# Main.net
KiCad netlist of a schematic drawn in EAGLE
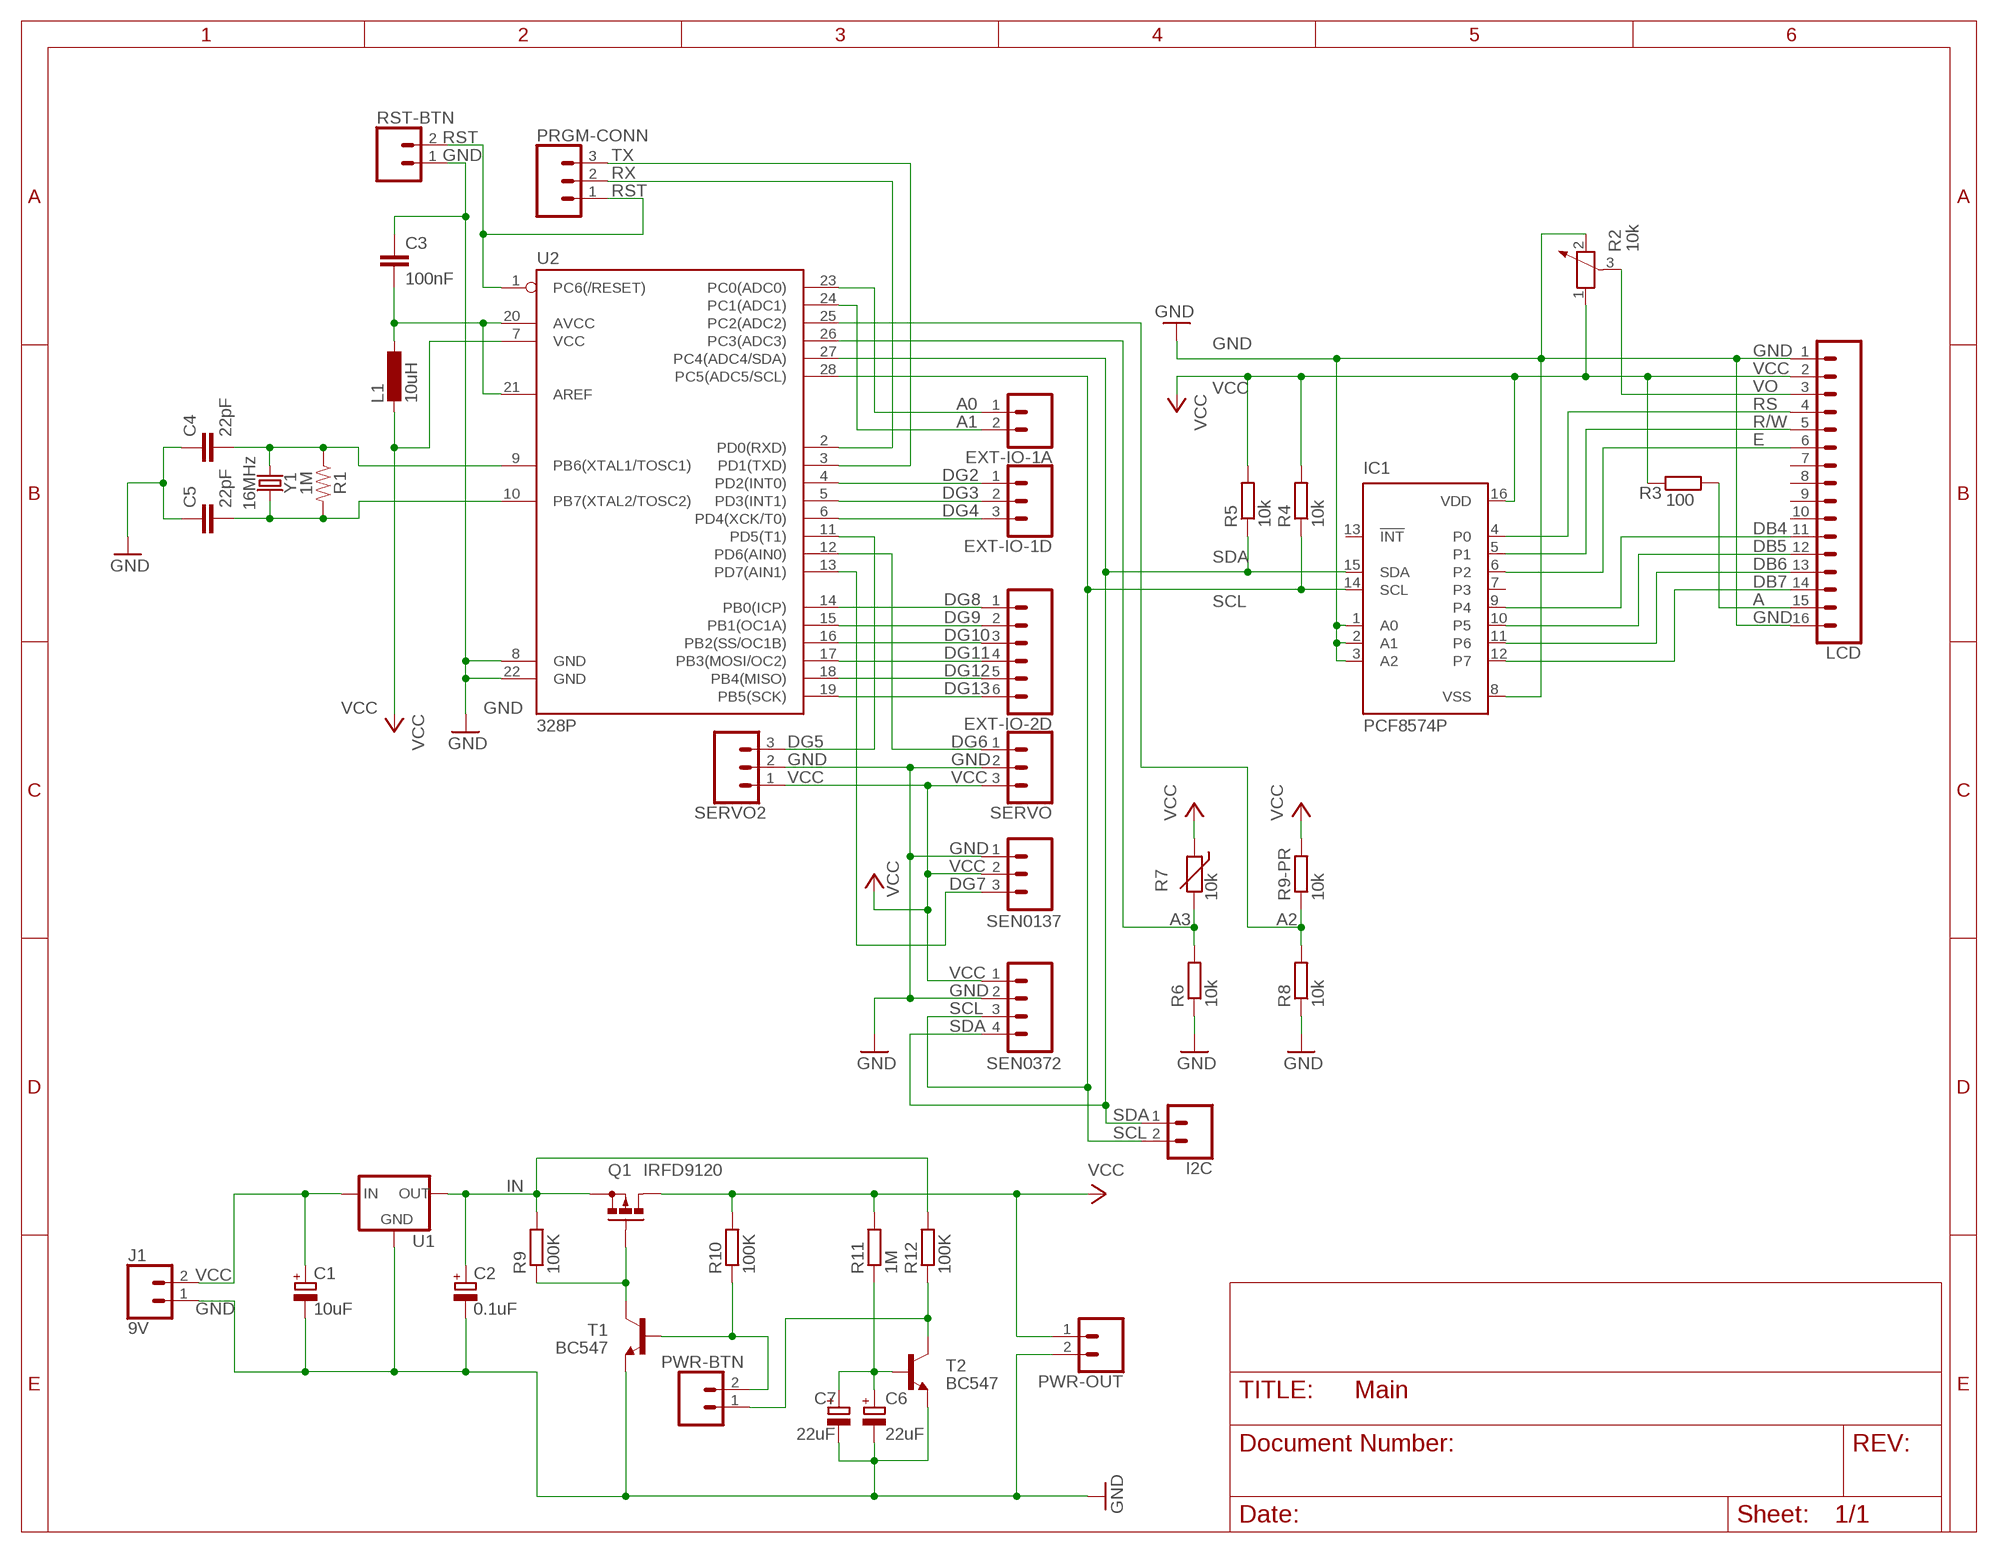
[diagram p0: schematic, sheet 1]

(export (version "E")
  (design (tool "Eeschema 10.0.6"))
  (components
    (comp (ref "C1")
      (value "10uF")
      (footprint "eagle-import:E2,5-5")
      (libsource (lib "eagle-import") (part "CPOL-EUE2.5-5"))
    )
    (comp (ref "C2")
      (value "0.1uF")
      (footprint "eagle-import:E2-4")
      (libsource (lib "eagle-import") (part "CPOL-EUE2-4"))
    )
    (comp (ref "C3")
      (value "100nF")
      (footprint "eagle-import:C050-025X075")
      (libsource (lib "eagle-import") (part "C-EU050-025X075"))
    )
    (comp (ref "C4")
      (value "22pF")
      (footprint "eagle-import:CAP-PTH-2.54")
      (libsource (lib "eagle-import") (part "22PF-PTH-2.54MM-200V-5%"))
    )
    (comp (ref "C5")
      (value "22pF")
      (footprint "eagle-import:CAP-PTH-2.54")
      (libsource (lib "eagle-import") (part "22PF-PTH-2.54MM-200V-5%"))
    )
    (comp (ref "C6")
      (value "22uF")
      (footprint "eagle-import:E2-5")
      (libsource (lib "eagle-import") (part "CPOL-EUE2-5"))
    )
    (comp (ref "C7")
      (value "22uF")
      (footprint "eagle-import:E2-5")
      (libsource (lib "eagle-import") (part "CPOL-EUE2-5"))
    )
    (comp (ref "EXT-IO-1A")
      (value "CONN_02LOCK_LONGPADS")
      (footprint "eagle-import:1X02_LOCK_LONGPADS")
      (libsource (lib "eagle-import") (part "CONN_02LOCK_LONGPADS"))
    )
    (comp (ref "EXT-IO-1D")
      (value "CONN_03LONGPADS")
      (footprint "eagle-import:1X03_LONGPADS")
      (libsource (lib "eagle-import") (part "CONN_03LONGPADS"))
    )
    (comp (ref "EXT-IO-2D")
      (value "CONN_06LONGPADS")
      (footprint "eagle-import:1X06_LONGPADS")
      (libsource (lib "eagle-import") (part "CONN_06LONGPADS"))
    )
    (comp (ref "I2C")
      (value "CONN_02LOCK_LONGPADS")
      (footprint "eagle-import:1X02_LOCK_LONGPADS")
      (libsource (lib "eagle-import") (part "CONN_02LOCK_LONGPADS"))
    )
    (comp (ref "IC1")
      (value "PCF8574P")
      (footprint "eagle-import:DIL16")
      (fields (field (name "MPN") "PCF8574PN"))
      (libsource (lib "eagle-import") (part "PCF8574P"))
    )
    (comp (ref "J1")
      (value "9V")
      (footprint "eagle-import:1X02_LOCK_LONGPADS")
      (libsource (lib "eagle-import") (part "CONN_02LOCK_LONGPADS"))
    )
    (comp (ref "L1")
      (value "10uH")
      (footprint "eagle-import:0204_5")
      (libsource (lib "eagle-import") (part "L-EU0204/5"))
    )
    (comp (ref "LCD")
      (value "CONN_16LONGPADS")
      (footprint "eagle-import:1X16_LONGPADS")
      (libsource (lib "eagle-import") (part "CONN_16LONGPADS"))
    )
    (comp (ref "PRGM-CONN")
      (value "CONN_03LONGPADS")
      (footprint "eagle-import:1X03_LONGPADS")
      (libsource (lib "eagle-import") (part "CONN_03LONGPADS"))
    )
    (comp (ref "PWR-BTN")
      (value "CONN_02LOCK_LONGPADS")
      (footprint "eagle-import:1X02_LOCK_LONGPADS")
      (libsource (lib "eagle-import") (part "CONN_02LOCK_LONGPADS"))
    )
    (comp (ref "PWR-OUT")
      (value "CONN_02LOCK_LONGPADS")
      (footprint "eagle-import:1X02_LOCK_LONGPADS")
      (libsource (lib "eagle-import") (part "CONN_02LOCK_LONGPADS"))
    )
    (comp (ref "Q1")
      (value "IRFD9120")
      (footprint "eagle-import:C370-01")
      (libsource (lib "eagle-import") (part "IRFD9120"))
    )
    (comp (ref "R1")
      (value "1M")
      (footprint "eagle-import:AXIAL-0.3")
      (libsource (lib "eagle-import") (part "RESISTORAXIAL-0.3"))
    )
    (comp (ref "R2")
      (value "10k")
      (footprint "eagle-import:PT-10")
      (libsource (lib "eagle-import") (part "POTENTIOMETER_PT-10"))
    )
    (comp (ref "R3")
      (value "100")
      (footprint "eagle-import:0207_10")
      (libsource (lib "eagle-import") (part "R-EU_0207/10"))
    )
    (comp (ref "R4")
      (value "10k")
      (footprint "eagle-import:0207_10")
      (libsource (lib "eagle-import") (part "R-EU_0207/10"))
    )
    (comp (ref "R5")
      (value "10k")
      (footprint "eagle-import:0207_10")
      (libsource (lib "eagle-import") (part "R-EU_0207/10"))
    )
    (comp (ref "R6")
      (value "10k")
      (footprint "eagle-import:0207_10")
      (libsource (lib "eagle-import") (part "R-EU_0207/10"))
    )
    (comp (ref "R7")
      (value "10k")
      (footprint "eagle-import:RS-2,5")
      (libsource (lib "eagle-import") (part "THERMISTOR-2,5"))
    )
    (comp (ref "R8")
      (value "10k")
      (footprint "eagle-import:0207_10")
      (libsource (lib "eagle-import") (part "R-EU_0207/10"))
    )
    (comp (ref "R9")
      (value "100K")
      (footprint "eagle-import:0207_10")
      (libsource (lib "eagle-import") (part "R-EU_0207/10"))
    )
    (comp (ref "R9-PR")
      (value "10k")
      (footprint "eagle-import:0204V")
      (libsource (lib "eagle-import") (part "R-EU_0204/2V"))
    )
    (comp (ref "R10")
      (value "100K")
      (footprint "eagle-import:0207_10")
      (libsource (lib "eagle-import") (part "R-EU_0207/10"))
    )
    (comp (ref "R11")
      (value "1M")
      (footprint "eagle-import:0207_10")
      (libsource (lib "eagle-import") (part "R-EU_0207/10"))
    )
    (comp (ref "R12")
      (value "100K")
      (footprint "eagle-import:0207_10")
      (libsource (lib "eagle-import") (part "R-EU_0207/10"))
    )
    (comp (ref "RST-BTN")
      (value "CONN_02LOCK_LONGPADS")
      (footprint "eagle-import:1X02_LOCK_LONGPADS")
      (libsource (lib "eagle-import") (part "CONN_02LOCK_LONGPADS"))
    )
    (comp (ref "SEN0137")
      (value "CONN_03LONGPADS")
      (footprint "eagle-import:1X03_LONGPADS")
      (libsource (lib "eagle-import") (part "CONN_03LONGPADS"))
    )
    (comp (ref "SEN0372")
      (value "CONN_04LONGPADS")
      (footprint "eagle-import:1X04_LONGPADS")
      (libsource (lib "eagle-import") (part "CONN_04LONGPADS"))
    )
    (comp (ref "SERVO")
      (value "CONN_03LONGPADS")
      (footprint "eagle-import:1X03_LONGPADS")
      (libsource (lib "eagle-import") (part "CONN_03LONGPADS"))
    )
    (comp (ref "SERVO2")
      (value "CONN_03LONGPADS")
      (footprint "eagle-import:1X03_LONGPADS")
      (libsource (lib "eagle-import") (part "CONN_03LONGPADS"))
    )
    (comp (ref "T1")
      (value "BC547")
      (footprint "eagle-import:TO92")
      (libsource (lib "eagle-import") (part "BC547"))
    )
    (comp (ref "T2")
      (value "BC547")
      (footprint "eagle-import:TO92")
      (libsource (lib "eagle-import") (part "BC547"))
    )
    (comp (ref "U1")
      (value "V_REG_78XX-TO-220")
      (footprint "eagle-import:TO-220-ALT")
      (libsource (lib "eagle-import") (part "V_REG_78XX-TO-220"))
    )
    (comp (ref "U2")
      (value "328P")
      (footprint "eagle-import:DIP28")
      (libsource (lib "eagle-import") (part "ATMEGA328P_PDIP"))
    )
    (comp (ref "Y1")
      (value "16MHz")
      (footprint "eagle-import:HC49US")
      (libsource (lib "eagle-import") (part "CRYSTAL-16MHZPTH-HC49US"))
    )
  )
  (nets
    (net (code "1") (name "/A") (class "Default")
      (node (ref "LCD") (pin "15") (pinfunction "15_15") (pintype "passive"))
      (node (ref "R3") (pin "2") (pinfunction "2_2") (pintype "passive"))
    )
    (net (code "2") (name "/A0") (class "Default")
      (node (ref "EXT-IO-1A") (pin "1") (pinfunction "1_1") (pintype "passive"))
      (node (ref "U2") (pin "23") (pinfunction "PC0(ADC0)_23") (pintype "bidirectional"))
    )
    (net (code "3") (name "/A1") (class "Default")
      (node (ref "EXT-IO-1A") (pin "2") (pinfunction "2_2") (pintype "passive"))
      (node (ref "U2") (pin "24") (pinfunction "PC1(ADC1)_24") (pintype "bidirectional"))
    )
    (net (code "4") (name "/A2") (class "Default")
      (node (ref "R8") (pin "2") (pinfunction "2_2") (pintype "passive"))
      (node (ref "R9-PR") (pin "1") (pinfunction "1_1") (pintype "passive"))
      (node (ref "U2") (pin "25") (pinfunction "PC2(ADC2)_25") (pintype "bidirectional"))
    )
    (net (code "5") (name "/A3") (class "Default")
      (node (ref "R6") (pin "2") (pinfunction "2_2") (pintype "passive"))
      (node (ref "R7") (pin "2") (pinfunction "2_2") (pintype "passive"))
      (node (ref "U2") (pin "26") (pinfunction "PC3(ADC3)_26") (pintype "bidirectional"))
    )
    (net (code "6") (name "/DB4") (class "Default")
      (node (ref "IC1") (pin "9") (pinfunction "P4_9") (pintype "bidirectional"))
      (node (ref "LCD") (pin "11") (pinfunction "11_11") (pintype "passive"))
    )
    (net (code "7") (name "/DB5") (class "Default")
      (node (ref "IC1") (pin "10") (pinfunction "P5_10") (pintype "bidirectional"))
      (node (ref "LCD") (pin "12") (pinfunction "12_12") (pintype "passive"))
    )
    (net (code "8") (name "/DB6") (class "Default")
      (node (ref "IC1") (pin "11") (pinfunction "P6_11") (pintype "bidirectional"))
      (node (ref "LCD") (pin "13") (pinfunction "13_13") (pintype "passive"))
    )
    (net (code "9") (name "/DB7") (class "Default")
      (node (ref "IC1") (pin "12") (pinfunction "P7_12") (pintype "bidirectional"))
      (node (ref "LCD") (pin "14") (pinfunction "14_14") (pintype "passive"))
    )
    (net (code "10") (name "/DG2") (class "Default")
      (node (ref "EXT-IO-1D") (pin "1") (pinfunction "1_1") (pintype "passive"))
      (node (ref "U2") (pin "4") (pinfunction "PD2(INT0)_4") (pintype "bidirectional"))
    )
    (net (code "11") (name "/DG3") (class "Default")
      (node (ref "EXT-IO-1D") (pin "2") (pinfunction "2_2") (pintype "passive"))
      (node (ref "U2") (pin "5") (pinfunction "PD3(INT1)_5") (pintype "bidirectional"))
    )
    (net (code "12") (name "/DG4") (class "Default")
      (node (ref "EXT-IO-1D") (pin "3") (pinfunction "3_3") (pintype "passive"))
      (node (ref "U2") (pin "6") (pinfunction "PD4(XCK/T0)_6") (pintype "bidirectional"))
    )
    (net (code "13") (name "/DG5") (class "Default")
      (node (ref "SERVO2") (pin "3") (pinfunction "3_3") (pintype "passive"))
      (node (ref "U2") (pin "11") (pinfunction "PD5(T1)_11") (pintype "bidirectional"))
    )
    (net (code "14") (name "/DG6") (class "Default")
      (node (ref "SERVO") (pin "1") (pinfunction "1_1") (pintype "passive"))
      (node (ref "U2") (pin "12") (pinfunction "PD6(AIN0)_12") (pintype "bidirectional"))
    )
    (net (code "15") (name "/DG7") (class "Default")
      (node (ref "SEN0137") (pin "3") (pinfunction "3_3") (pintype "passive"))
      (node (ref "U2") (pin "13") (pinfunction "PD7(AIN1)_13") (pintype "bidirectional"))
    )
    (net (code "16") (name "/DG8") (class "Default")
      (node (ref "EXT-IO-2D") (pin "1") (pinfunction "1_1") (pintype "passive"))
      (node (ref "U2") (pin "14") (pinfunction "PB0(ICP)_14") (pintype "bidirectional"))
    )
    (net (code "17") (name "/DG9") (class "Default")
      (node (ref "EXT-IO-2D") (pin "2") (pinfunction "2_2") (pintype "passive"))
      (node (ref "U2") (pin "15") (pinfunction "PB1(OC1A)_15") (pintype "bidirectional"))
    )
    (net (code "18") (name "/DG10") (class "Default")
      (node (ref "EXT-IO-2D") (pin "3") (pinfunction "3_3") (pintype "passive"))
      (node (ref "U2") (pin "16") (pinfunction "PB2(SS/OC1B)_16") (pintype "bidirectional"))
    )
    (net (code "19") (name "/DG11") (class "Default")
      (node (ref "EXT-IO-2D") (pin "4") (pinfunction "4_4") (pintype "passive"))
      (node (ref "U2") (pin "17") (pinfunction "PB3(MOSI/OC2)_17") (pintype "bidirectional"))
    )
    (net (code "20") (name "/DG12") (class "Default")
      (node (ref "EXT-IO-2D") (pin "5") (pinfunction "5_5") (pintype "passive"))
      (node (ref "U2") (pin "18") (pinfunction "PB4(MISO)_18") (pintype "bidirectional"))
    )
    (net (code "21") (name "/DG13") (class "Default")
      (node (ref "EXT-IO-2D") (pin "6") (pinfunction "6_6") (pintype "passive"))
      (node (ref "U2") (pin "19") (pinfunction "PB5(SCK)_19") (pintype "bidirectional"))
    )
    (net (code "22") (name "/E") (class "Default")
      (node (ref "IC1") (pin "6") (pinfunction "P2_6") (pintype "bidirectional"))
      (node (ref "LCD") (pin "6") (pinfunction "6_6") (pintype "passive"))
    )
    (net (code "23") (name "/IN") (class "Default")
      (node (ref "C2") (pin "+") (pinfunction "+_+") (pintype "passive"))
      (node (ref "Q1") (pin "S") (pinfunction "S_S") (pintype "passive"))
      (node (ref "R12") (pin "2") (pinfunction "2_2") (pintype "passive"))
      (node (ref "R9") (pin "2") (pinfunction "2_2") (pintype "passive"))
      (node (ref "U1") (pin "OUT") (pinfunction "OUT_OUT") (pintype "passive"))
    )
    (net (code "24") (name "/RS") (class "Default")
      (node (ref "IC1") (pin "4") (pinfunction "P0_4") (pintype "bidirectional"))
      (node (ref "LCD") (pin "4") (pinfunction "4_4") (pintype "passive"))
    )
    (net (code "25") (name "/RST") (class "Default")
      (node (ref "PRGM-CONN") (pin "1") (pinfunction "1_1") (pintype "passive"))
      (node (ref "RST-BTN") (pin "2") (pinfunction "2_2") (pintype "passive"))
      (node (ref "U2") (pin "1") (pinfunction "PC6(/RESET)_1") (pintype "bidirectional"))
    )
    (net (code "26") (name "/RX") (class "Default")
      (node (ref "PRGM-CONN") (pin "2") (pinfunction "2_2") (pintype "passive"))
      (node (ref "U2") (pin "2") (pinfunction "PD0(RXD)_2") (pintype "bidirectional"))
    )
    (net (code "27") (name "/R{slash}W") (class "Default")
      (node (ref "IC1") (pin "5") (pinfunction "P1_5") (pintype "bidirectional"))
      (node (ref "LCD") (pin "5") (pinfunction "5_5") (pintype "passive"))
    )
    (net (code "28") (name "/SCL") (class "Default")
      (node (ref "I2C") (pin "2") (pinfunction "2_2") (pintype "passive"))
      (node (ref "IC1") (pin "14") (pinfunction "SCL_14") (pintype "input"))
      (node (ref "R4") (pin "1") (pinfunction "1_1") (pintype "passive"))
      (node (ref "SEN0372") (pin "3") (pinfunction "3_3") (pintype "passive"))
      (node (ref "U2") (pin "28") (pinfunction "PC5(ADC5/SCL)_28") (pintype "bidirectional"))
    )
    (net (code "29") (name "/SDA") (class "Default")
      (node (ref "I2C") (pin "1") (pinfunction "1_1") (pintype "passive"))
      (node (ref "IC1") (pin "15") (pinfunction "SDA_15") (pintype "bidirectional"))
      (node (ref "R5") (pin "1") (pinfunction "1_1") (pintype "passive"))
      (node (ref "SEN0372") (pin "4") (pinfunction "4_4") (pintype "passive"))
      (node (ref "U2") (pin "27") (pinfunction "PC4(ADC4/SDA)_27") (pintype "bidirectional"))
    )
    (net (code "30") (name "/TX") (class "Default")
      (node (ref "PRGM-CONN") (pin "3") (pinfunction "3_3") (pintype "passive"))
      (node (ref "U2") (pin "3") (pinfunction "PD1(TXD)_3") (pintype "bidirectional"))
    )
    (net (code "31") (name "/VO") (class "Default")
      (node (ref "LCD") (pin "3") (pinfunction "3_3") (pintype "passive"))
      (node (ref "R2") (pin "3") (pinfunction "3_3") (pintype "passive"))
    )
    (net (code "32") (name "GND") (class "Default")
      (node (ref "C1") (pin "-") (pinfunction "-_-") (pintype "passive"))
      (node (ref "C2") (pin "-") (pinfunction "-_-") (pintype "passive"))
      (node (ref "C3") (pin "1") (pinfunction "1_1") (pintype "passive"))
      (node (ref "C4") (pin "1") (pinfunction "1_1") (pintype "passive"))
      (node (ref "C5") (pin "1") (pinfunction "1_1") (pintype "passive"))
      (node (ref "C6") (pin "-") (pinfunction "-_-") (pintype "passive"))
      (node (ref "C7") (pin "-") (pinfunction "-_-") (pintype "passive"))
      (node (ref "IC1") (pin "1") (pinfunction "A0_1") (pintype "input"))
      (node (ref "IC1") (pin "2") (pinfunction "A1_2") (pintype "input"))
      (node (ref "IC1") (pin "3") (pinfunction "A2_3") (pintype "input"))
      (node (ref "IC1") (pin "8") (pinfunction "VSS_8") (pintype "power_in"))
      (node (ref "J1") (pin "1") (pinfunction "1_1") (pintype "passive"))
      (node (ref "LCD") (pin "1") (pinfunction "1_1") (pintype "passive"))
      (node (ref "LCD") (pin "16") (pinfunction "16_16") (pintype "passive"))
      (node (ref "PWR-OUT") (pin "2") (pinfunction "2_2") (pintype "passive"))
      (node (ref "R2") (pin "2") (pinfunction "2_2") (pintype "passive"))
      (node (ref "R6") (pin "1") (pinfunction "1_1") (pintype "passive"))
      (node (ref "R8") (pin "1") (pinfunction "1_1") (pintype "passive"))
      (node (ref "RST-BTN") (pin "1") (pinfunction "1_1") (pintype "passive"))
      (node (ref "SEN0137") (pin "1") (pinfunction "1_1") (pintype "passive"))
      (node (ref "SEN0372") (pin "2") (pinfunction "2_2") (pintype "passive"))
      (node (ref "SERVO") (pin "2") (pinfunction "2_2") (pintype "passive"))
      (node (ref "SERVO2") (pin "2") (pinfunction "2_2") (pintype "passive"))
      (node (ref "T1") (pin "1") (pinfunction "E_1") (pintype "passive"))
      (node (ref "T2") (pin "1") (pinfunction "E_1") (pintype "passive"))
      (node (ref "U1") (pin "GND") (pinfunction "GND_GND") (pintype "input"))
      (node (ref "U2") (pin "22") (pinfunction "GND_22") (pintype "bidirectional"))
      (node (ref "U2") (pin "8") (pinfunction "GND_8") (pintype "bidirectional"))
    )
    (net (code "33") (name "Net-(R1-1)") (class "Default")
      (node (ref "C4") (pin "2") (pinfunction "2_2") (pintype "passive"))
      (node (ref "R1") (pin "P$1") (pinfunction "1_P$1") (pintype "passive"))
      (node (ref "U2") (pin "9") (pinfunction "PB6(XTAL1/TOSC1)_9") (pintype "bidirectional"))
      (node (ref "Y1") (pin "1") (pinfunction "1_1") (pintype "passive"))
    )
    (net (code "34") (name "Net-(R1-2)") (class "Default")
      (node (ref "C5") (pin "2") (pinfunction "2_2") (pintype "passive"))
      (node (ref "R1") (pin "P$2") (pinfunction "2_P$2") (pintype "passive"))
      (node (ref "U2") (pin "10") (pinfunction "PB7(XTAL2/TOSC2)_10") (pintype "bidirectional"))
      (node (ref "Y1") (pin "2") (pinfunction "2_2") (pintype "passive"))
    )
    (net (code "35") (name "Net-(T1-B)") (class "Default")
      (node (ref "PWR-BTN") (pin "2") (pinfunction "2_2") (pintype "passive"))
      (node (ref "R10") (pin "1") (pinfunction "1_1") (pintype "passive"))
      (node (ref "T1") (pin "2") (pinfunction "B_2") (pintype "passive"))
    )
    (net (code "36") (name "Net-(T1-C)") (class "Default")
      (node (ref "Q1") (pin "G") (pinfunction "G_G") (pintype "passive"))
      (node (ref "R9") (pin "1") (pinfunction "1_1") (pintype "passive"))
      (node (ref "T1") (pin "3") (pinfunction "C_3") (pintype "passive"))
    )
    (net (code "37") (name "Net-(T2-B)") (class "Default")
      (node (ref "C6") (pin "+") (pinfunction "+_+") (pintype "passive"))
      (node (ref "C7") (pin "+") (pinfunction "+_+") (pintype "passive"))
      (node (ref "R11") (pin "1") (pinfunction "1_1") (pintype "passive"))
      (node (ref "T2") (pin "2") (pinfunction "B_2") (pintype "passive"))
    )
    (net (code "38") (name "Net-(T2-C)") (class "Default")
      (node (ref "PWR-BTN") (pin "1") (pinfunction "1_1") (pintype "passive"))
      (node (ref "R12") (pin "1") (pinfunction "1_1") (pintype "passive"))
      (node (ref "T2") (pin "3") (pinfunction "C_3") (pintype "passive"))
    )
    (net (code "39") (name "Net-(U2-AREF)") (class "Default")
      (node (ref "C3") (pin "2") (pinfunction "2_2") (pintype "passive"))
      (node (ref "L1") (pin "1") (pinfunction "1_1") (pintype "passive"))
      (node (ref "U2") (pin "20") (pinfunction "AVCC_20") (pintype "bidirectional"))
      (node (ref "U2") (pin "21") (pinfunction "AREF_21") (pintype "bidirectional"))
    )
    (net (code "40") (name "VCC") (class "Default")
      (node (ref "C1") (pin "+") (pinfunction "+_+") (pintype "passive"))
      (node (ref "IC1") (pin "16") (pinfunction "VDD_16") (pintype "power_in"))
      (node (ref "J1") (pin "2") (pinfunction "2_2") (pintype "passive"))
      (node (ref "L1") (pin "2") (pinfunction "2_2") (pintype "passive"))
      (node (ref "LCD") (pin "2") (pinfunction "2_2") (pintype "passive"))
      (node (ref "PWR-OUT") (pin "1") (pinfunction "1_1") (pintype "passive"))
      (node (ref "Q1") (pin "D") (pinfunction "D_D") (pintype "passive"))
      (node (ref "Q1") (pin "D1") (pinfunction "D_D1") (pintype "passive"))
      (node (ref "R10") (pin "2") (pinfunction "2_2") (pintype "passive"))
      (node (ref "R11") (pin "2") (pinfunction "2_2") (pintype "passive"))
      (node (ref "R2") (pin "1") (pinfunction "1_1") (pintype "passive"))
      (node (ref "R3") (pin "1") (pinfunction "1_1") (pintype "passive"))
      (node (ref "R4") (pin "2") (pinfunction "2_2") (pintype "passive"))
      (node (ref "R5") (pin "2") (pinfunction "2_2") (pintype "passive"))
      (node (ref "R7") (pin "1") (pinfunction "1_1") (pintype "passive"))
      (node (ref "R9-PR") (pin "2") (pinfunction "2_2") (pintype "passive"))
      (node (ref "SEN0137") (pin "2") (pinfunction "2_2") (pintype "passive"))
      (node (ref "SEN0372") (pin "1") (pinfunction "1_1") (pintype "passive"))
      (node (ref "SERVO") (pin "3") (pinfunction "3_3") (pintype "passive"))
      (node (ref "SERVO2") (pin "1") (pinfunction "1_1") (pintype "passive"))
      (node (ref "U1") (pin "IN") (pinfunction "IN_IN") (pintype "input"))
      (node (ref "U2") (pin "7") (pinfunction "VCC_7") (pintype "bidirectional"))
    )
    (net (code "41") (name "unconnected-(IC1-P3-Pad7)") (class "Default")
      (node (ref "IC1") (pin "7") (pinfunction "P3_7") (pintype "bidirectional"))
    )
    (net (code "42") (name "unconnected-(IC1-~{INT}-Pad13)") (class "Default")
      (node (ref "IC1") (pin "13") (pinfunction "~{INT}_13") (pintype "output"))
    )
    (net (code "43") (name "unconnected-(LCD-Pad7)") (class "Default")
      (node (ref "LCD") (pin "7") (pinfunction "7_7") (pintype "passive"))
    )
    (net (code "44") (name "unconnected-(LCD-Pad8)") (class "Default")
      (node (ref "LCD") (pin "8") (pinfunction "8_8") (pintype "passive"))
    )
    (net (code "45") (name "unconnected-(LCD-Pad9)") (class "Default")
      (node (ref "LCD") (pin "9") (pinfunction "9_9") (pintype "passive"))
    )
    (net (code "46") (name "unconnected-(LCD-Pad10)") (class "Default")
      (node (ref "LCD") (pin "10") (pinfunction "10_10") (pintype "passive"))
    )
  )
)
